# SCH___2024-01-21.net
KiCad netlist of a schematic drawn in EasyEDA
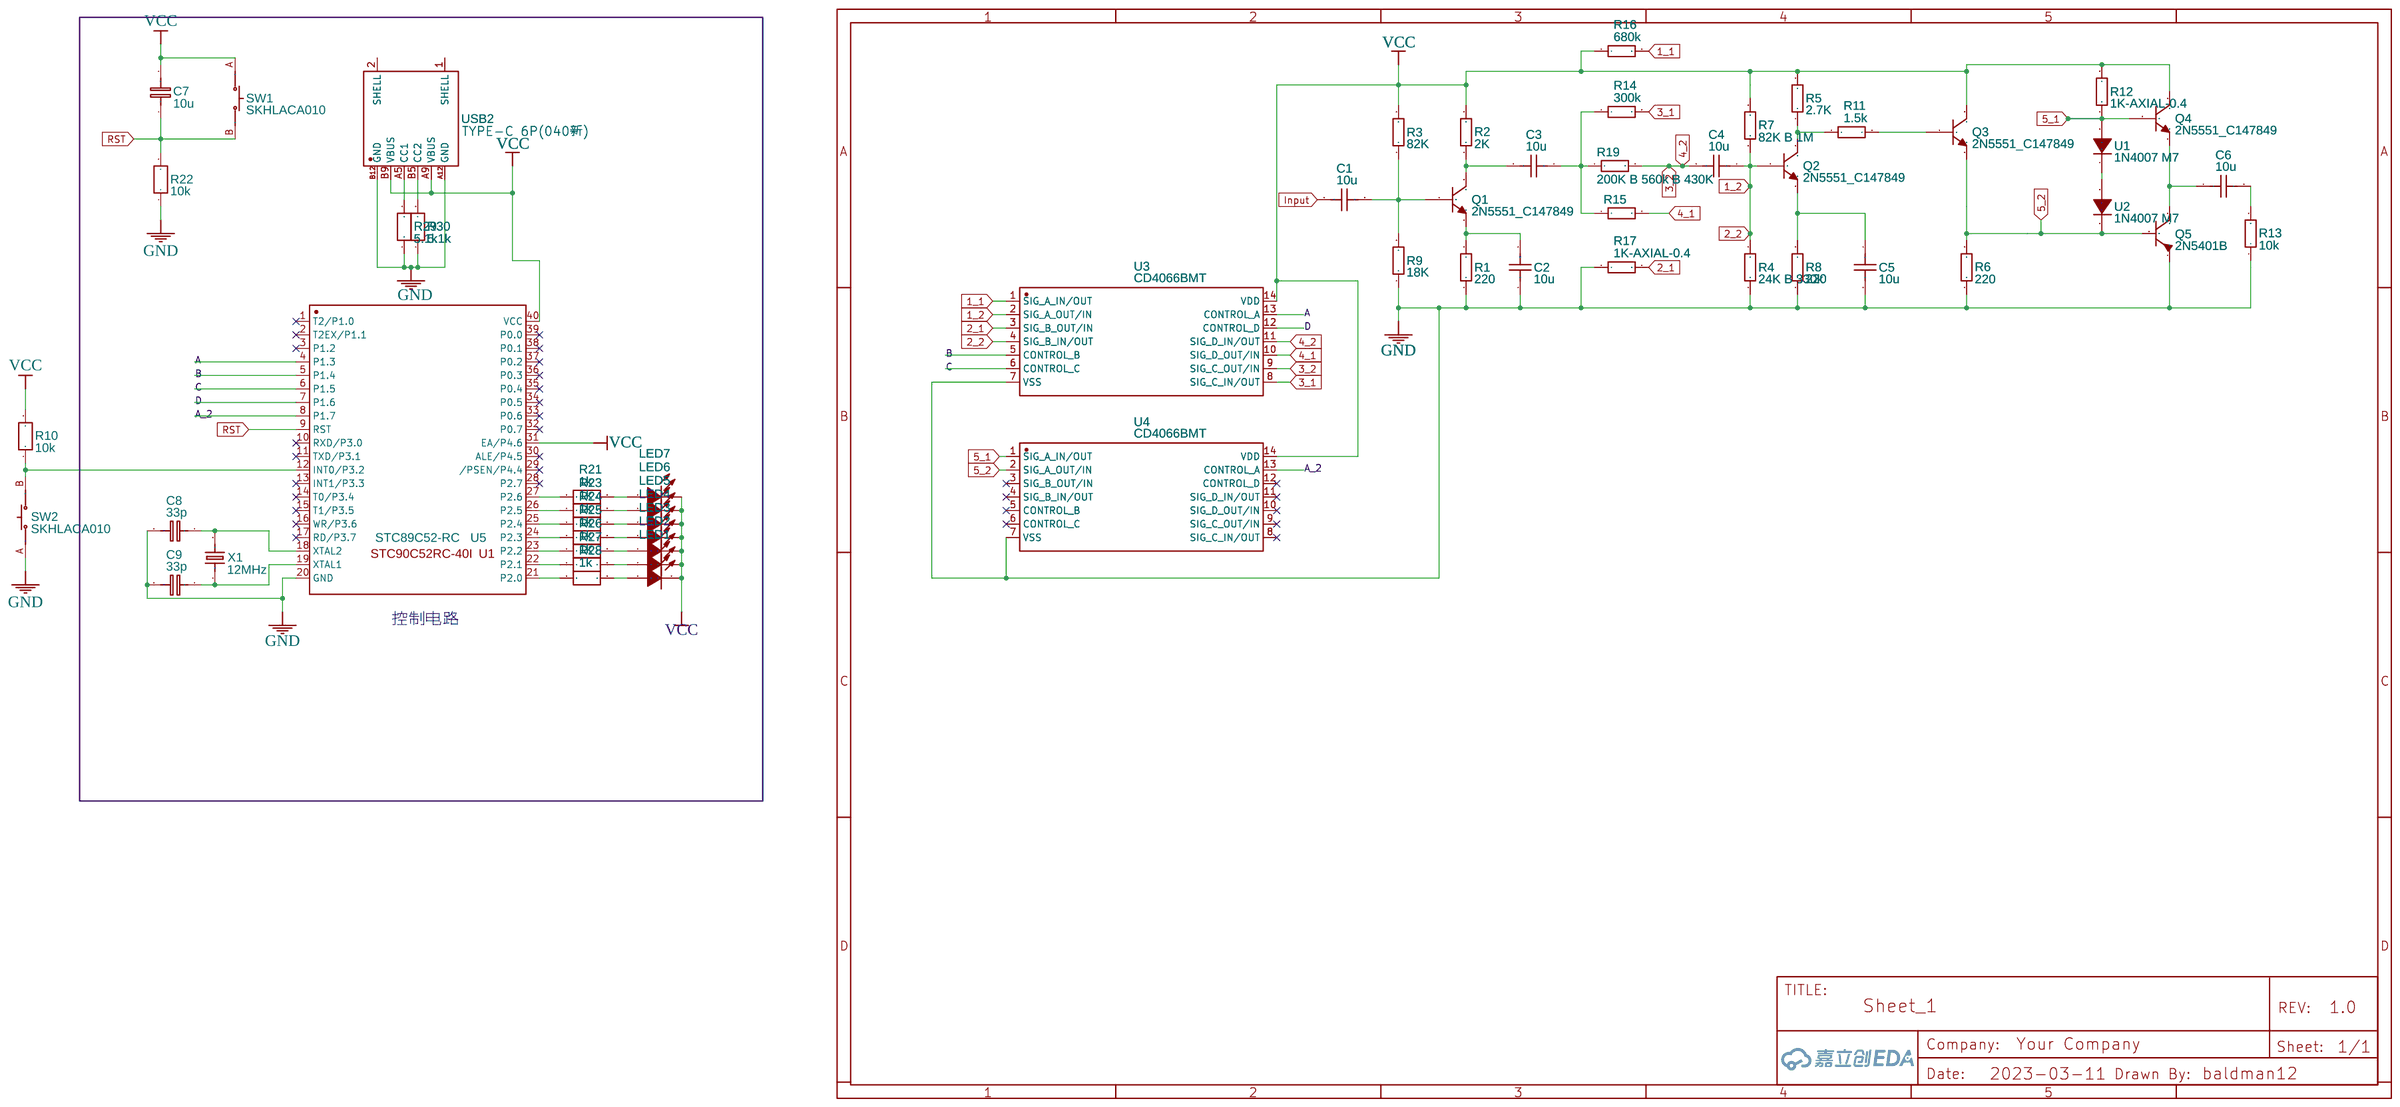
[diagram p0: schematic sheet]

(export (version "E")
  (design (tool "Eeschema 10.0.6"))
  (components
    (comp (ref "C1") (value "10u") (libsource (lib "") (part "C_0603_US_1")))
    (comp (ref "C2") (value "10u") (libsource (lib "") (part "C_0603_US_3")))
    (comp (ref "C3") (value "10u") (libsource (lib "") (part "C_0603_US")))
    (comp (ref "C4") (value "10u") (libsource (lib "") (part "C_0603_US")))
    (comp (ref "C5") (value "10u") (libsource (lib "") (part "C_0603_US_2")))
    (comp (ref "C6") (value "10u") (libsource (lib "") (part "C_0603_US_1")))
    (comp (ref "C7") (value "10u") (libsource (lib "") (part "C_0603_EU_1")))
    (comp (ref "C8") (value "33p") (libsource (lib "") (part "C_0603_EU")))
    (comp (ref "C9") (value "33p") (libsource (lib "") (part "C_0603_EU")))
    (comp (ref "LED1")
      (value "204-10SURC/S530-A3-L")
      (fields (field (name "Manufacturer") "EVERLIGHT(亿光)"))
      (libsource (lib "") (part "204-10SURC/S530-A3-L"))
    )
    (comp (ref "LED2")
      (value "204-10SURC/S530-A3-L")
      (fields (field (name "Manufacturer") "EVERLIGHT(亿光)"))
      (libsource (lib "") (part "204-10SURC/S530-A3-L"))
    )
    (comp (ref "LED3")
      (value "204-10SURC/S530-A3-L")
      (fields (field (name "Manufacturer") "EVERLIGHT(亿光)"))
      (libsource (lib "") (part "204-10SURC/S530-A3-L"))
    )
    (comp (ref "LED4")
      (value "204-10SURC/S530-A3-L")
      (fields (field (name "Manufacturer") "EVERLIGHT(亿光)"))
      (libsource (lib "") (part "204-10SURC/S530-A3-L"))
    )
    (comp (ref "LED5")
      (value "204-10SURC/S530-A3-L")
      (fields (field (name "Manufacturer") "EVERLIGHT(亿光)"))
      (libsource (lib "") (part "204-10SURC/S530-A3-L"))
    )
    (comp (ref "LED6")
      (value "204-10SURC/S530-A3-L")
      (fields (field (name "Manufacturer") "EVERLIGHT(亿光)"))
      (libsource (lib "") (part "204-10SURC/S530-A3-L"))
    )
    (comp (ref "LED7")
      (value "204-10SURC/S530-A3-L")
      (fields (field (name "Manufacturer") "EVERLIGHT(亿光)"))
      (libsource (lib "") (part "204-10SURC/S530-A3-L"))
    )
    (comp (ref "Q1")
      (value "2N5551_C147849")
      (fields (field (name "Manufacturer Part") "2N5551") (field (name "Manufacturer") "CJ(江苏长电/长晶)"))
      (libsource (lib "") (part "2N5551_C147849"))
    )
    (comp (ref "Q2")
      (value "2N5551_C147849")
      (fields (field (name "Manufacturer Part") "2N5551") (field (name "Manufacturer") "CJ(江苏长电/长晶)"))
      (libsource (lib "") (part "2N5551_C147849"))
    )
    (comp (ref "Q3")
      (value "2N5551_C147849")
      (fields (field (name "Manufacturer Part") "2N5551") (field (name "Manufacturer") "CJ(江苏长电/长晶)"))
      (libsource (lib "") (part "2N5551_C147849"))
    )
    (comp (ref "Q4")
      (value "2N5551_C147849")
      (fields (field (name "Manufacturer Part") "2N5551") (field (name "Manufacturer") "CJ(江苏长电/长晶)"))
      (libsource (lib "") (part "2N5551_C147849"))
    )
    (comp (ref "Q5")
      (value "2N5401B")
      (fields (field (name "Manufacturer") "FeiHong(飞虹)"))
      (libsource (lib "") (part "2N5401B"))
    )
    (comp (ref "R1")
      (value "220")
      (fields (field (name "Manufacturer Part") "1K-AXIAL-0.4"))
      (libsource (lib "") (part "1K-AXIAL-0.4_1"))
    )
    (comp (ref "R2")
      (value "2K")
      (fields (field (name "Manufacturer Part") "1K-AXIAL-0.4"))
      (libsource (lib "") (part "1K-AXIAL-0.4_1"))
    )
    (comp (ref "R3")
      (value "82K")
      (fields (field (name "Manufacturer Part") "1K-AXIAL-0.4"))
      (libsource (lib "") (part "1K-AXIAL-0.4_1"))
    )
    (comp (ref "R4")
      (value "24K B 330k")
      (fields (field (name "Manufacturer Part") "1K-AXIAL-0.4"))
      (libsource (lib "") (part "1K-AXIAL-0.4_1"))
    )
    (comp (ref "R5")
      (value "2.7K")
      (fields (field (name "Manufacturer Part") "1K-AXIAL-0.4"))
      (libsource (lib "") (part "1K-AXIAL-0.4_1"))
    )
    (comp (ref "R6")
      (value "220")
      (fields (field (name "Manufacturer Part") "1K-AXIAL-0.4"))
      (libsource (lib "") (part "1K-AXIAL-0.4_1"))
    )
    (comp (ref "R7")
      (value "82K B 1M")
      (fields (field (name "Manufacturer Part") "1K-AXIAL-0.4"))
      (libsource (lib "") (part "1K-AXIAL-0.4_1"))
    )
    (comp (ref "R8")
      (value "220")
      (fields (field (name "Manufacturer Part") "1K-AXIAL-0.4"))
      (libsource (lib "") (part "1K-AXIAL-0.4_1"))
    )
    (comp (ref "R9")
      (value "18K")
      (fields (field (name "Manufacturer Part") "1K-AXIAL-0.4"))
      (libsource (lib "") (part "1K-AXIAL-0.4_1"))
    )
    (comp (ref "R10") (value "10k") (libsource (lib "") (part "R_0603_EU")))
    (comp (ref "R11")
      (value "1.5k")
      (fields (field (name "Manufacturer Part") "1K-AXIAL-0.4"))
      (libsource (lib "") (part "1K-AXIAL-0.4"))
    )
    (comp (ref "R12") (value "1K-AXIAL-0.4") (libsource (lib "") (part "1K-AXIAL-0.4_1")))
    (comp (ref "R13")
      (value "10k")
      (fields (field (name "Manufacturer Part") "1K-AXIAL-0.4"))
      (libsource (lib "") (part "1K-AXIAL-0.4_1"))
    )
    (comp (ref "R14")
      (value "300k")
      (fields (field (name "Manufacturer Part") "1K-AXIAL-0.4"))
      (libsource (lib "") (part "1K-AXIAL-0.4"))
    )
    (comp (ref "R15") (value "1K-AXIAL-0.4") (libsource (lib "") (part "1K-AXIAL-0.4")))
    (comp (ref "R16")
      (value "680k")
      (fields (field (name "Manufacturer Part") "1K-AXIAL-0.4"))
      (libsource (lib "") (part "1K-AXIAL-0.4"))
    )
    (comp (ref "R17") (value "1K-AXIAL-0.4") (libsource (lib "") (part "1K-AXIAL-0.4")))
    (comp (ref "R19")
      (value "200K B 560k B 430K")
      (fields (field (name "Manufacturer Part") "1K-AXIAL-0.4"))
      (libsource (lib "") (part "1K-AXIAL-0.4"))
    )
    (comp (ref "R21") (value "1k") (libsource (lib "") (part "R_0603_EU_1")))
    (comp (ref "R22") (value "10k") (libsource (lib "") (part "R_0603_EU")))
    (comp (ref "R23") (value "1k") (libsource (lib "") (part "R_0603_EU_1")))
    (comp (ref "R24") (value "1k") (libsource (lib "") (part "R_0603_EU_1")))
    (comp (ref "R25") (value "1k") (libsource (lib "") (part "R_0603_EU_1")))
    (comp (ref "R26") (value "1k") (libsource (lib "") (part "R_0603_EU_1")))
    (comp (ref "R27") (value "1k") (libsource (lib "") (part "R_0603_EU_1")))
    (comp (ref "R28") (value "1k") (libsource (lib "") (part "R_0603_EU_1")))
    (comp (ref "R29") (value "5.1k") (libsource (lib "") (part "R_0603_EU")))
    (comp (ref "R30") (value "5.1k") (libsource (lib "") (part "R_0603_EU")))
    (comp (ref "SW1")
      (value "SKHLACA010")
      (fields (field (name "Manufacturer") "ALPSALPINE(阿尔卑斯阿尔派)"))
      (libsource (lib "") (part "SKHLACA010_1"))
    )
    (comp (ref "SW2")
      (value "SKHLACA010")
      (fields (field (name "Manufacturer") "ALPSALPINE(阿尔卑斯阿尔派)"))
      (libsource (lib "") (part "SKHLACA010"))
    )
    (comp (ref "U1") (value "1N4007 M7") (libsource (lib "") (part "1N4007 M7")))
    (comp (ref "U2") (value "1N4007 M7") (libsource (lib "") (part "1N4007 M7")))
    (comp (ref "U3")
      (value "CD4066BMT")
      (fields (field (name "Manufacturer") "TI(德州仪器)"))
      (libsource (lib "") (part "CD4066BMT"))
    )
    (comp (ref "U4")
      (value "CD4066BMT")
      (fields (field (name "Manufacturer") "TI(德州仪器)"))
      (libsource (lib "") (part "CD4066BMT"))
    )
    (comp (ref "U5") (value "STC89C52-RC") (libsource (lib "") (part "STC89C52-RC")))
    (comp (ref "USB2")
      (value "TYPE-C 6P(040新)")
      (fields (field (name "Manufacturer") "SHOU HAN(首韩)"))
      (libsource (lib "") (part "TYPE-C 6P(040新)"))
    )
    (comp (ref "X1")
      (value "12MHz")
      (fields (field (name "Manufacturer Part") "TAXD12M2GLFBET2T") (field (name "Manufacturer") "TAE(雅晶鑫)"))
      (libsource (lib "") (part "HC-49S12MHZ20PF30PPM"))
    )
  )
  (nets
    (net (code "1") (name "/A") (class "Default")
      (node (ref "U3") (pin "13") (pinfunction "CONTROL_A_13") (pintype "unspecified"))
      (node (ref "U5") (pin "4") (pinfunction "P1.3_4") (pintype "unspecified"))
    )
    (net (code "2") (name "/A_2") (class "Default")
      (node (ref "U4") (pin "13") (pinfunction "CONTROL_A_13") (pintype "unspecified"))
      (node (ref "U5") (pin "8") (pinfunction "P1.7_8") (pintype "unspecified"))
    )
    (net (code "3") (name "/B") (class "Default")
      (node (ref "U3") (pin "5") (pinfunction "CONTROL_B_5") (pintype "unspecified"))
      (node (ref "U5") (pin "5") (pinfunction "P1.4_5") (pintype "unspecified"))
    )
    (net (code "4") (name "/C") (class "Default")
      (node (ref "U3") (pin "6") (pinfunction "CONTROL_C_6") (pintype "unspecified"))
      (node (ref "U5") (pin "6") (pinfunction "P1.5_6") (pintype "unspecified"))
    )
    (net (code "5") (name "/D") (class "Default")
      (node (ref "U3") (pin "12") (pinfunction "CONTROL_D_12") (pintype "unspecified"))
      (node (ref "U5") (pin "7") (pinfunction "P1.6_7") (pintype "unspecified"))
    )
    (net (code "6") (name "1_1") (class "Default")
      (node (ref "R16") (pin "2") (pinfunction "2_2") (pintype "unspecified"))
      (node (ref "U3") (pin "1") (pinfunction "SIG_A_IN/OUT_1") (pintype "unspecified"))
    )
    (net (code "7") (name "1_2") (class "Default")
      (node (ref "C4") (pin "1") (pinfunction "1_1") (pintype "unspecified"))
      (node (ref "Q2") (pin "2") (pinfunction "B_2") (pintype "unspecified"))
      (node (ref "R4") (pin "2") (pinfunction "2_2") (pintype "unspecified"))
      (node (ref "R7") (pin "1") (pinfunction "1_1") (pintype "unspecified"))
      (node (ref "U3") (pin "2") (pinfunction "SIG_A_OUT/IN_2") (pintype "unspecified"))
      (node (ref "U3") (pin "4") (pinfunction "SIG_B_IN/OUT_4") (pintype "unspecified"))
    )
    (net (code "8") (name "2_1") (class "Default")
      (node (ref "R17") (pin "2") (pinfunction "2_2") (pintype "unspecified"))
      (node (ref "U3") (pin "3") (pinfunction "SIG_B_OUT/IN_3") (pintype "unspecified"))
    )
    (net (code "9") (name "3_1") (class "Default")
      (node (ref "R14") (pin "2") (pinfunction "2_2") (pintype "unspecified"))
      (node (ref "U3") (pin "8") (pinfunction "SIG_C_IN/OUT_8") (pintype "unspecified"))
    )
    (net (code "10") (name "3_2") (class "Default")
      (node (ref "C4") (pin "2") (pinfunction "2_2") (pintype "unspecified"))
      (node (ref "R19") (pin "2") (pinfunction "2_2") (pintype "unspecified"))
      (node (ref "U3") (pin "11") (pinfunction "SIG_D_IN/OUT_11") (pintype "unspecified"))
      (node (ref "U3") (pin "9") (pinfunction "SIG_C_OUT/IN_9") (pintype "unspecified"))
    )
    (net (code "11") (name "4_1") (class "Default")
      (node (ref "R15") (pin "2") (pinfunction "2_2") (pintype "unspecified"))
      (node (ref "U3") (pin "10") (pinfunction "SIG_D_OUT/IN_10") (pintype "unspecified"))
    )
    (net (code "12") (name "5_1") (class "Default")
      (node (ref "Q4") (pin "2") (pinfunction "B_2") (pintype "unspecified"))
      (node (ref "R12") (pin "1") (pinfunction "1_1") (pintype "unspecified"))
      (node (ref "U1") (pin "2") (pinfunction "A_2") (pintype "unspecified"))
      (node (ref "U4") (pin "1") (pinfunction "SIG_A_IN/OUT_1") (pintype "unspecified"))
    )
    (net (code "13") (name "5_2") (class "Default")
      (node (ref "Q3") (pin "1") (pinfunction "E_1") (pintype "unspecified"))
      (node (ref "Q5") (pin "2") (pinfunction "B_2") (pintype "unspecified"))
      (node (ref "R6") (pin "2") (pinfunction "2_2") (pintype "unspecified"))
      (node (ref "U2") (pin "1") (pinfunction "K_1") (pintype "unspecified"))
      (node (ref "U4") (pin "2") (pinfunction "SIG_A_OUT/IN_2") (pintype "unspecified"))
    )
    (net (code "14") (name "GND") (class "Default")
      (node (ref "C2") (pin "1") (pinfunction "1_1") (pintype "unspecified"))
      (node (ref "C5") (pin "2") (pinfunction "2_2") (pintype "unspecified"))
      (node (ref "C8") (pin "2") (pinfunction "2_2") (pintype "unspecified"))
      (node (ref "C9") (pin "2") (pinfunction "2_2") (pintype "unspecified"))
      (node (ref "Q5") (pin "1") (pinfunction "E_1") (pintype "unspecified"))
      (node (ref "R1") (pin "1") (pinfunction "1_1") (pintype "unspecified"))
      (node (ref "R13") (pin "1") (pinfunction "1_1") (pintype "unspecified"))
      (node (ref "R17") (pin "1") (pinfunction "1_1") (pintype "unspecified"))
      (node (ref "R22") (pin "1") (pinfunction "1_1") (pintype "unspecified"))
      (node (ref "R29") (pin "1") (pinfunction "1_1") (pintype "unspecified"))
      (node (ref "R30") (pin "1") (pinfunction "1_1") (pintype "unspecified"))
      (node (ref "R4") (pin "1") (pinfunction "1_1") (pintype "unspecified"))
      (node (ref "R6") (pin "1") (pinfunction "1_1") (pintype "unspecified"))
      (node (ref "R8") (pin "1") (pinfunction "1_1") (pintype "unspecified"))
      (node (ref "R9") (pin "1") (pinfunction "1_1") (pintype "unspecified"))
      (node (ref "SW2") (pin "A") (pinfunction "A_A") (pintype "unspecified"))
      (node (ref "U3") (pin "7") (pinfunction "VSS_7") (pintype "unspecified"))
      (node (ref "U4") (pin "7") (pinfunction "VSS_7") (pintype "unspecified"))
      (node (ref "U5") (pin "20") (pinfunction "GND_20") (pintype "unspecified"))
      (node (ref "USB2") (pin "A12") (pinfunction "GND_A12") (pintype "unspecified"))
      (node (ref "USB2") (pin "B12") (pinfunction "GND_B12") (pintype "unspecified"))
    )
    (net (code "15") (name "Input") (class "Default")
      (node (ref "C1") (pin "1") (pinfunction "1_1") (pintype "unspecified"))
    )
    (net (code "16") (name "Net-(C3-Pad1)") (class "Default")
      (node (ref "C3") (pin "1") (pinfunction "1_1") (pintype "unspecified"))
      (node (ref "R14") (pin "1") (pinfunction "1_1") (pintype "unspecified"))
      (node (ref "R15") (pin "1") (pinfunction "1_1") (pintype "unspecified"))
      (node (ref "R19") (pin "1") (pinfunction "1_1") (pintype "unspecified"))
    )
    (net (code "17") (name "Net-(C6-Pad2)") (class "Default")
      (node (ref "C6") (pin "2") (pinfunction "2_2") (pintype "unspecified"))
      (node (ref "R13") (pin "2") (pinfunction "2_2") (pintype "unspecified"))
    )
    (net (code "18") (name "Net-(LED1-A)") (class "Default")
      (node (ref "LED1") (pin "1") (pinfunction "A_1") (pintype "unspecified"))
      (node (ref "R28") (pin "2") (pinfunction "2_2") (pintype "unspecified"))
    )
    (net (code "19") (name "Net-(LED2-A)") (class "Default")
      (node (ref "LED2") (pin "1") (pinfunction "A_1") (pintype "unspecified"))
      (node (ref "R27") (pin "2") (pinfunction "2_2") (pintype "unspecified"))
    )
    (net (code "20") (name "Net-(LED3-A)") (class "Default")
      (node (ref "LED3") (pin "1") (pinfunction "A_1") (pintype "unspecified"))
      (node (ref "R26") (pin "2") (pinfunction "2_2") (pintype "unspecified"))
    )
    (net (code "21") (name "Net-(LED4-A)") (class "Default")
      (node (ref "LED4") (pin "1") (pinfunction "A_1") (pintype "unspecified"))
      (node (ref "R25") (pin "2") (pinfunction "2_2") (pintype "unspecified"))
    )
    (net (code "22") (name "Net-(LED5-A)") (class "Default")
      (node (ref "LED5") (pin "1") (pinfunction "A_1") (pintype "unspecified"))
      (node (ref "R24") (pin "2") (pinfunction "2_2") (pintype "unspecified"))
    )
    (net (code "23") (name "Net-(LED6-A)") (class "Default")
      (node (ref "LED6") (pin "1") (pinfunction "A_1") (pintype "unspecified"))
      (node (ref "R23") (pin "2") (pinfunction "2_2") (pintype "unspecified"))
    )
    (net (code "24") (name "Net-(LED7-A)") (class "Default")
      (node (ref "LED7") (pin "1") (pinfunction "A_1") (pintype "unspecified"))
      (node (ref "R21") (pin "2") (pinfunction "2_2") (pintype "unspecified"))
    )
    (net (code "25") (name "Net-(Q1-B)") (class "Default")
      (node (ref "C1") (pin "2") (pinfunction "2_2") (pintype "unspecified"))
      (node (ref "Q1") (pin "2") (pinfunction "B_2") (pintype "unspecified"))
      (node (ref "R3") (pin "1") (pinfunction "1_1") (pintype "unspecified"))
      (node (ref "R9") (pin "2") (pinfunction "2_2") (pintype "unspecified"))
    )
    (net (code "26") (name "Net-(Q1-C)") (class "Default")
      (node (ref "C3") (pin "2") (pinfunction "2_2") (pintype "unspecified"))
      (node (ref "Q1") (pin "3") (pinfunction "C_3") (pintype "unspecified"))
      (node (ref "R2") (pin "1") (pinfunction "1_1") (pintype "unspecified"))
    )
    (net (code "27") (name "Net-(Q1-E)") (class "Default")
      (node (ref "C2") (pin "2") (pinfunction "2_2") (pintype "unspecified"))
      (node (ref "Q1") (pin "1") (pinfunction "E_1") (pintype "unspecified"))
      (node (ref "R1") (pin "2") (pinfunction "2_2") (pintype "unspecified"))
    )
    (net (code "28") (name "Net-(Q2-C)") (class "Default")
      (node (ref "Q2") (pin "3") (pinfunction "C_3") (pintype "unspecified"))
      (node (ref "R11") (pin "1") (pinfunction "1_1") (pintype "unspecified"))
      (node (ref "R5") (pin "1") (pinfunction "1_1") (pintype "unspecified"))
    )
    (net (code "29") (name "Net-(Q2-E)") (class "Default")
      (node (ref "C5") (pin "1") (pinfunction "1_1") (pintype "unspecified"))
      (node (ref "Q2") (pin "1") (pinfunction "E_1") (pintype "unspecified"))
      (node (ref "R8") (pin "2") (pinfunction "2_2") (pintype "unspecified"))
    )
    (net (code "30") (name "Net-(Q3-B)") (class "Default")
      (node (ref "Q3") (pin "2") (pinfunction "B_2") (pintype "unspecified"))
      (node (ref "R11") (pin "2") (pinfunction "2_2") (pintype "unspecified"))
    )
    (net (code "31") (name "Net-(Q4-E)") (class "Default")
      (node (ref "C6") (pin "1") (pinfunction "1_1") (pintype "unspecified"))
      (node (ref "Q4") (pin "1") (pinfunction "E_1") (pintype "unspecified"))
      (node (ref "Q5") (pin "3") (pinfunction "C_3") (pintype "unspecified"))
    )
    (net (code "32") (name "Net-(U1-K)") (class "Default")
      (node (ref "U1") (pin "1") (pinfunction "K_1") (pintype "unspecified"))
      (node (ref "U2") (pin "2") (pinfunction "A_2") (pintype "unspecified"))
    )
    (net (code "33") (name "Net-(U5-INT0{slash}P3.2)") (class "Default")
      (node (ref "R10") (pin "1") (pinfunction "1_1") (pintype "unspecified"))
      (node (ref "SW2") (pin "B") (pinfunction "B_B") (pintype "unspecified"))
      (node (ref "U5") (pin "12") (pinfunction "INT0/P3.2_12") (pintype "unspecified"))
    )
    (net (code "34") (name "Net-(U5-P2.0)") (class "Default")
      (node (ref "R28") (pin "1") (pinfunction "1_1") (pintype "unspecified"))
      (node (ref "U5") (pin "21") (pinfunction "P2.0_21") (pintype "unspecified"))
    )
    (net (code "35") (name "Net-(U5-P2.1)") (class "Default")
      (node (ref "R27") (pin "1") (pinfunction "1_1") (pintype "unspecified"))
      (node (ref "U5") (pin "22") (pinfunction "P2.1_22") (pintype "unspecified"))
    )
    (net (code "36") (name "Net-(U5-P2.2)") (class "Default")
      (node (ref "R26") (pin "1") (pinfunction "1_1") (pintype "unspecified"))
      (node (ref "U5") (pin "23") (pinfunction "P2.2_23") (pintype "unspecified"))
    )
    (net (code "37") (name "Net-(U5-P2.3)") (class "Default")
      (node (ref "R25") (pin "1") (pinfunction "1_1") (pintype "unspecified"))
      (node (ref "U5") (pin "24") (pinfunction "P2.3_24") (pintype "unspecified"))
    )
    (net (code "38") (name "Net-(U5-P2.4)") (class "Default")
      (node (ref "R24") (pin "1") (pinfunction "1_1") (pintype "unspecified"))
      (node (ref "U5") (pin "25") (pinfunction "P2.4_25") (pintype "unspecified"))
    )
    (net (code "39") (name "Net-(U5-P2.5)") (class "Default")
      (node (ref "R23") (pin "1") (pinfunction "1_1") (pintype "unspecified"))
      (node (ref "U5") (pin "26") (pinfunction "P2.5_26") (pintype "unspecified"))
    )
    (net (code "40") (name "Net-(U5-P2.6)") (class "Default")
      (node (ref "R21") (pin "1") (pinfunction "1_1") (pintype "unspecified"))
      (node (ref "U5") (pin "27") (pinfunction "P2.6_27") (pintype "unspecified"))
    )
    (net (code "41") (name "Net-(U5-XTAL1)") (class "Default")
      (node (ref "C9") (pin "1") (pinfunction "1_1") (pintype "unspecified"))
      (node (ref "U5") (pin "19") (pinfunction "XTAL1_19") (pintype "unspecified"))
      (node (ref "X1") (pin "1") (pinfunction "1_1") (pintype "unspecified"))
    )
    (net (code "42") (name "Net-(U5-XTAL2)") (class "Default")
      (node (ref "C8") (pin "1") (pinfunction "1_1") (pintype "unspecified"))
      (node (ref "U5") (pin "18") (pinfunction "XTAL2_18") (pintype "unspecified"))
      (node (ref "X1") (pin "2") (pinfunction "2_2") (pintype "unspecified"))
    )
    (net (code "43") (name "Net-(USB2-CC1)") (class "Default")
      (node (ref "R29") (pin "2") (pinfunction "2_2") (pintype "unspecified"))
      (node (ref "USB2") (pin "A5") (pinfunction "CC1_A5") (pintype "unspecified"))
    )
    (net (code "44") (name "Net-(USB2-CC2)") (class "Default")
      (node (ref "R30") (pin "2") (pinfunction "2_2") (pintype "unspecified"))
      (node (ref "USB2") (pin "B5") (pinfunction "CC2_B5") (pintype "unspecified"))
    )
    (net (code "45") (name "RST") (class "Default")
      (node (ref "C7") (pin "1") (pinfunction "1_1") (pintype "unspecified"))
      (node (ref "R22") (pin "2") (pinfunction "2_2") (pintype "unspecified"))
      (node (ref "SW1") (pin "B") (pinfunction "B_B") (pintype "unspecified"))
      (node (ref "U5") (pin "9") (pinfunction "RST_9") (pintype "unspecified"))
    )
    (net (code "46") (name "VCC") (class "Default")
      (node (ref "C7") (pin "2") (pinfunction "2_2") (pintype "unspecified"))
      (node (ref "LED1") (pin "2") (pinfunction "K_2") (pintype "unspecified"))
      (node (ref "LED2") (pin "2") (pinfunction "K_2") (pintype "unspecified"))
      (node (ref "LED3") (pin "2") (pinfunction "K_2") (pintype "unspecified"))
      (node (ref "LED4") (pin "2") (pinfunction "K_2") (pintype "unspecified"))
      (node (ref "LED5") (pin "2") (pinfunction "K_2") (pintype "unspecified"))
      (node (ref "LED6") (pin "2") (pinfunction "K_2") (pintype "unspecified"))
      (node (ref "LED7") (pin "2") (pinfunction "K_2") (pintype "unspecified"))
      (node (ref "Q3") (pin "3") (pinfunction "C_3") (pintype "unspecified"))
      (node (ref "Q4") (pin "3") (pinfunction "C_3") (pintype "unspecified"))
      (node (ref "R10") (pin "2") (pinfunction "2_2") (pintype "unspecified"))
      (node (ref "R12") (pin "2") (pinfunction "2_2") (pintype "unspecified"))
      (node (ref "R16") (pin "1") (pinfunction "1_1") (pintype "unspecified"))
      (node (ref "R2") (pin "2") (pinfunction "2_2") (pintype "unspecified"))
      (node (ref "R3") (pin "2") (pinfunction "2_2") (pintype "unspecified"))
      (node (ref "R5") (pin "2") (pinfunction "2_2") (pintype "unspecified"))
      (node (ref "R7") (pin "2") (pinfunction "2_2") (pintype "unspecified"))
      (node (ref "SW1") (pin "A") (pinfunction "A_A") (pintype "unspecified"))
      (node (ref "U3") (pin "14") (pinfunction "VDD_14") (pintype "unspecified"))
      (node (ref "U4") (pin "14") (pinfunction "VDD_14") (pintype "unspecified"))
      (node (ref "U5") (pin "31") (pinfunction "EA/P4.6_31") (pintype "unspecified"))
      (node (ref "U5") (pin "40") (pinfunction "VCC_40") (pintype "unspecified"))
      (node (ref "USB2") (pin "A9") (pinfunction "VBUS_A9") (pintype "unspecified"))
      (node (ref "USB2") (pin "B9") (pinfunction "VBUS_B9") (pintype "unspecified"))
    )
    (net (code "47") (name "unconnected-(U4-CONTROL_B-Pad5)") (class "Default")
      (node (ref "U4") (pin "5") (pinfunction "CONTROL_B_5") (pintype "unspecified+no_connect"))
    )
    (net (code "48") (name "unconnected-(U4-CONTROL_C-Pad6)") (class "Default")
      (node (ref "U4") (pin "6") (pinfunction "CONTROL_C_6") (pintype "unspecified+no_connect"))
    )
    (net (code "49") (name "unconnected-(U4-CONTROL_D-Pad12)") (class "Default")
      (node (ref "U4") (pin "12") (pinfunction "CONTROL_D_12") (pintype "unspecified+no_connect"))
    )
    (net (code "50") (name "unconnected-(U4-SIG_B_IN{slash}OUT-Pad4)") (class "Default")
      (node (ref "U4") (pin "4") (pinfunction "SIG_B_IN/OUT_4") (pintype "unspecified+no_connect"))
    )
    (net (code "51") (name "unconnected-(U4-SIG_B_OUT{slash}IN-Pad3)") (class "Default")
      (node (ref "U4") (pin "3") (pinfunction "SIG_B_OUT/IN_3") (pintype "unspecified+no_connect"))
    )
    (net (code "52") (name "unconnected-(U4-SIG_C_IN{slash}OUT-Pad8)") (class "Default")
      (node (ref "U4") (pin "8") (pinfunction "SIG_C_IN/OUT_8") (pintype "unspecified+no_connect"))
    )
    (net (code "53") (name "unconnected-(U4-SIG_C_OUT{slash}IN-Pad9)") (class "Default")
      (node (ref "U4") (pin "9") (pinfunction "SIG_C_OUT/IN_9") (pintype "unspecified+no_connect"))
    )
    (net (code "54") (name "unconnected-(U4-SIG_D_IN{slash}OUT-Pad11)") (class "Default")
      (node (ref "U4") (pin "11") (pinfunction "SIG_D_IN/OUT_11") (pintype "unspecified+no_connect"))
    )
    (net (code "55") (name "unconnected-(U4-SIG_D_OUT{slash}IN-Pad10)") (class "Default")
      (node (ref "U4") (pin "10") (pinfunction "SIG_D_OUT/IN_10") (pintype "unspecified+no_connect"))
    )
    (net (code "56") (name "unconnected-(U5-ALE{slash}P4.5-Pad30)") (class "Default")
      (node (ref "U5") (pin "30") (pinfunction "ALE/P4.5_30") (pintype "unspecified+no_connect"))
    )
    (net (code "57") (name "unconnected-(U5-INT1{slash}P3.3-Pad13)") (class "Default")
      (node (ref "U5") (pin "13") (pinfunction "INT1/P3.3_13") (pintype "unspecified+no_connect"))
    )
    (net (code "58") (name "unconnected-(U5-P0.0-Pad39)") (class "Default")
      (node (ref "U5") (pin "39") (pinfunction "P0.0_39") (pintype "unspecified+no_connect"))
    )
    (net (code "59") (name "unconnected-(U5-P0.1-Pad38)") (class "Default")
      (node (ref "U5") (pin "38") (pinfunction "P0.1_38") (pintype "unspecified+no_connect"))
    )
    (net (code "60") (name "unconnected-(U5-P0.2-Pad37)") (class "Default")
      (node (ref "U5") (pin "37") (pinfunction "P0.2_37") (pintype "unspecified+no_connect"))
    )
    (net (code "61") (name "unconnected-(U5-P0.3-Pad36)") (class "Default")
      (node (ref "U5") (pin "36") (pinfunction "P0.3_36") (pintype "unspecified+no_connect"))
    )
    (net (code "62") (name "unconnected-(U5-P0.4-Pad35)") (class "Default")
      (node (ref "U5") (pin "35") (pinfunction "P0.4_35") (pintype "unspecified+no_connect"))
    )
    (net (code "63") (name "unconnected-(U5-P0.5-Pad34)") (class "Default")
      (node (ref "U5") (pin "34") (pinfunction "P0.5_34") (pintype "unspecified+no_connect"))
    )
    (net (code "64") (name "unconnected-(U5-P0.6-Pad33)") (class "Default")
      (node (ref "U5") (pin "33") (pinfunction "P0.6_33") (pintype "unspecified+no_connect"))
    )
    (net (code "65") (name "unconnected-(U5-P0.7-Pad32)") (class "Default")
      (node (ref "U5") (pin "32") (pinfunction "P0.7_32") (pintype "unspecified+no_connect"))
    )
    (net (code "66") (name "unconnected-(U5-P1.2-Pad3)") (class "Default")
      (node (ref "U5") (pin "3") (pinfunction "P1.2_3") (pintype "unspecified+no_connect"))
    )
    (net (code "67") (name "unconnected-(U5-P2.7-Pad28)") (class "Default")
      (node (ref "U5") (pin "28") (pinfunction "P2.7_28") (pintype "unspecified+no_connect"))
    )
    (net (code "68") (name "unconnected-(U5-RD{slash}P3.7-Pad17)") (class "Default")
      (node (ref "U5") (pin "17") (pinfunction "RD/P3.7_17") (pintype "unspecified+no_connect"))
    )
    (net (code "69") (name "unconnected-(U5-RXD{slash}P3.0-Pad10)") (class "Default")
      (node (ref "U5") (pin "10") (pinfunction "RXD/P3.0_10") (pintype "unspecified+no_connect"))
    )
    (net (code "70") (name "unconnected-(U5-T0{slash}P3.4-Pad14)") (class "Default")
      (node (ref "U5") (pin "14") (pinfunction "T0/P3.4_14") (pintype "unspecified+no_connect"))
    )
    (net (code "71") (name "unconnected-(U5-T1{slash}P3.5-Pad15)") (class "Default")
      (node (ref "U5") (pin "15") (pinfunction "T1/P3.5_15") (pintype "unspecified+no_connect"))
    )
    (net (code "72") (name "unconnected-(U5-T2EX{slash}P1.1-Pad2)") (class "Default")
      (node (ref "U5") (pin "2") (pinfunction "T2EX/P1.1_2") (pintype "unspecified+no_connect"))
    )
    (net (code "73") (name "unconnected-(U5-T2{slash}P1.0-Pad1)") (class "Default")
      (node (ref "U5") (pin "1") (pinfunction "T2/P1.0_1") (pintype "unspecified+no_connect"))
    )
    (net (code "74") (name "unconnected-(U5-TXD{slash}P3.1-Pad11)") (class "Default")
      (node (ref "U5") (pin "11") (pinfunction "TXD/P3.1_11") (pintype "unspecified+no_connect"))
    )
    (net (code "75") (name "unconnected-(U5-WR{slash}P3.6-Pad16)") (class "Default")
      (node (ref "U5") (pin "16") (pinfunction "WR/P3.6_16") (pintype "unspecified+no_connect"))
    )
    (net (code "76") (name "unconnected-(U5-{slash}PSEN{slash}P4.4-Pad29)") (class "Default")
      (node (ref "U5") (pin "29") (pinfunction "/PSEN/P4.4_29") (pintype "unspecified+no_connect"))
    )
    (net (code "77") (name "unconnected-(USB2-SHELL-Pad1)") (class "Default")
      (node (ref "USB2") (pin "1") (pinfunction "SHELL_1") (pintype "unspecified"))
    )
    (net (code "78") (name "unconnected-(USB2-SHELL-Pad2)") (class "Default")
      (node (ref "USB2") (pin "2") (pinfunction "SHELL_2") (pintype "unspecified"))
    )
  )
)
